# PCB_Dpad_Trigger.net
KiCad netlist of a schematic drawn in Altium Designer
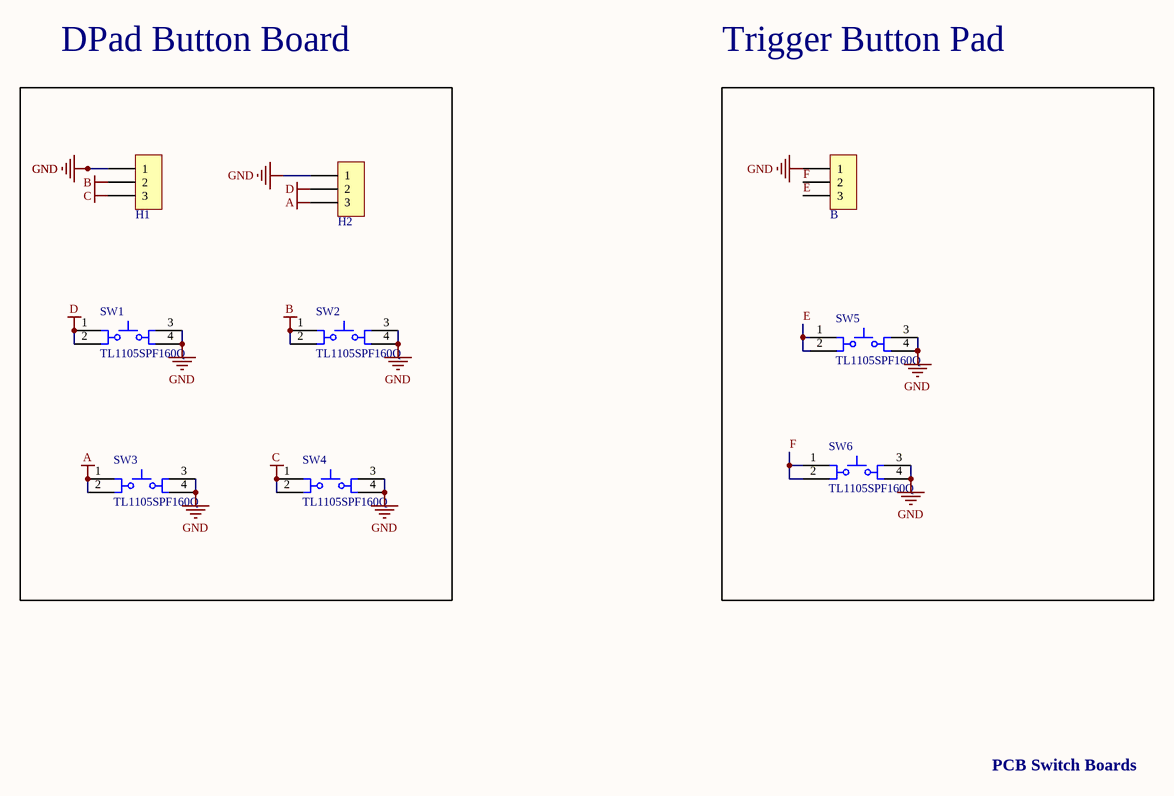
[diagram p0: PCB_Dpad&Trigger.SchDoc]

(export (version "E")
  (design (tool "Eeschema 10.0.6"))
  (components
    (comp (ref "B")
      (value "HDR,2.54mm,1x3")
      (footprint "APSS Connectors:HEADER_2.54MM_1x3PIN")
      (description "Connector - 2.54mm, 1x3-pin")
      (libsource (lib "APSS Connectors") (part "HDR,2.54mm,1x3"))
    )
    (comp (ref "H1")
      (value "HDR,2.54mm,1x3")
      (footprint "APSS Connectors:HEADER_2.54MM_1x3PIN")
      (description "Connector - 2.54mm, 1x3-pin")
      (libsource (lib "APSS Connectors") (part "HDR,2.54mm,1x3"))
    )
    (comp (ref "H2")
      (value "HDR,2.54mm,1x3")
      (footprint "APSS Connectors:HEADER_2.54MM_1x3PIN")
      (description "Connector - 2.54mm, 1x3-pin")
      (libsource (lib "APSS Connectors") (part "HDR,2.54mm,1x3"))
    )
    (comp (ref "SW1")
      (value "TL1105SPF160Q")
      (footprint "ESWI-TL1105SPF_V")
      (description "Tact Switch, SPST-NO, 50 mA, 12 VDC, -20 to 70 degC, 4-Pin THD, RoHS, Bulk")
      (fields (field (name "MANUFACTURER") "E-Switch"))
      (libsource (lib "New tactile switch") (part "CMP-2000-07248-1"))
    )
    (comp (ref "SW2")
      (value "TL1105SPF160Q")
      (footprint "ESWI-TL1105SPF_V")
      (description "Tact Switch, SPST-NO, 50 mA, 12 VDC, -20 to 70 degC, 4-Pin THD, RoHS, Bulk")
      (fields (field (name "MANUFACTURER") "E-Switch"))
      (libsource (lib "New tactile switch") (part "CMP-2000-07248-1"))
    )
    (comp (ref "SW3")
      (value "TL1105SPF160Q")
      (footprint "ESWI-TL1105SPF_V")
      (description "Tact Switch, SPST-NO, 50 mA, 12 VDC, -20 to 70 degC, 4-Pin THD, RoHS, Bulk")
      (fields (field (name "MANUFACTURER") "E-Switch"))
      (libsource (lib "New tactile switch") (part "CMP-2000-07248-1"))
    )
    (comp (ref "SW4")
      (value "TL1105SPF160Q")
      (footprint "ESWI-TL1105SPF_V")
      (description "Tact Switch, SPST-NO, 50 mA, 12 VDC, -20 to 70 degC, 4-Pin THD, RoHS, Bulk")
      (fields (field (name "MANUFACTURER") "E-Switch"))
      (libsource (lib "New tactile switch") (part "CMP-2000-07248-1"))
    )
    (comp (ref "SW5")
      (value "TL1105SPF160Q")
      (footprint "ESWI-TL1105SPF_V")
      (description "Tact Switch, SPST-NO, 50 mA, 12 VDC, -20 to 70 degC, 4-Pin THD, RoHS, Bulk")
      (fields (field (name "MANUFACTURER") "E-Switch"))
      (libsource (lib "New tactile switch") (part "CMP-2000-07248-1"))
    )
    (comp (ref "SW6")
      (value "TL1105SPF160Q")
      (footprint "ESWI-TL1105SPF_V")
      (description "Tact Switch, SPST-NO, 50 mA, 12 VDC, -20 to 70 degC, 4-Pin THD, RoHS, Bulk")
      (fields (field (name "MANUFACTURER") "E-Switch"))
      (libsource (lib "New tactile switch") (part "CMP-2000-07248-1"))
    )
  )
  (nets
    (net (code "1") (name "/E") (class "Default")
      (node (ref "B") (pin "3") (pinfunction "3_3") (pintype "passive"))
      (node (ref "SW5") (pin "1") (pinfunction "1_1") (pintype "passive"))
      (node (ref "SW5") (pin "2") (pinfunction "2_2") (pintype "passive"))
    )
    (net (code "2") (name "/F") (class "Default")
      (node (ref "B") (pin "2") (pinfunction "2_2") (pintype "passive"))
      (node (ref "SW6") (pin "1") (pinfunction "1_1") (pintype "passive"))
      (node (ref "SW6") (pin "2") (pinfunction "2_2") (pintype "passive"))
    )
    (net (code "3") (name "A") (class "Default")
      (node (ref "H2") (pin "3") (pinfunction "3_3") (pintype "passive"))
      (node (ref "SW3") (pin "1") (pinfunction "1_1") (pintype "passive"))
      (node (ref "SW3") (pin "2") (pinfunction "2_2") (pintype "passive"))
    )
    (net (code "4") (name "B") (class "Default")
      (node (ref "H1") (pin "2") (pinfunction "2_2") (pintype "passive"))
      (node (ref "SW2") (pin "1") (pinfunction "1_1") (pintype "passive"))
      (node (ref "SW2") (pin "2") (pinfunction "2_2") (pintype "passive"))
    )
    (net (code "5") (name "C") (class "Default")
      (node (ref "H1") (pin "3") (pinfunction "3_3") (pintype "passive"))
      (node (ref "SW4") (pin "1") (pinfunction "1_1") (pintype "passive"))
      (node (ref "SW4") (pin "2") (pinfunction "2_2") (pintype "passive"))
    )
    (net (code "6") (name "D") (class "Default")
      (node (ref "H2") (pin "2") (pinfunction "2_2") (pintype "passive"))
      (node (ref "SW1") (pin "1") (pinfunction "1_1") (pintype "passive"))
      (node (ref "SW1") (pin "2") (pinfunction "2_2") (pintype "passive"))
    )
    (net (code "7") (name "GND") (class "Default")
      (node (ref "B") (pin "1") (pinfunction "1_1") (pintype "passive"))
      (node (ref "H1") (pin "1") (pinfunction "1_1") (pintype "passive"))
      (node (ref "H2") (pin "1") (pinfunction "1_1") (pintype "passive"))
      (node (ref "SW1") (pin "3") (pinfunction "3_3") (pintype "passive"))
      (node (ref "SW1") (pin "4") (pinfunction "4_4") (pintype "passive"))
      (node (ref "SW2") (pin "3") (pinfunction "3_3") (pintype "passive"))
      (node (ref "SW2") (pin "4") (pinfunction "4_4") (pintype "passive"))
      (node (ref "SW3") (pin "3") (pinfunction "3_3") (pintype "passive"))
      (node (ref "SW3") (pin "4") (pinfunction "4_4") (pintype "passive"))
      (node (ref "SW4") (pin "3") (pinfunction "3_3") (pintype "passive"))
      (node (ref "SW4") (pin "4") (pinfunction "4_4") (pintype "passive"))
      (node (ref "SW5") (pin "3") (pinfunction "3_3") (pintype "passive"))
      (node (ref "SW5") (pin "4") (pinfunction "4_4") (pintype "passive"))
      (node (ref "SW6") (pin "3") (pinfunction "3_3") (pintype "passive"))
      (node (ref "SW6") (pin "4") (pinfunction "4_4") (pintype "passive"))
    )
  )
)
